# LineSense.net
KiCad netlist of a schematic drawn in EAGLE
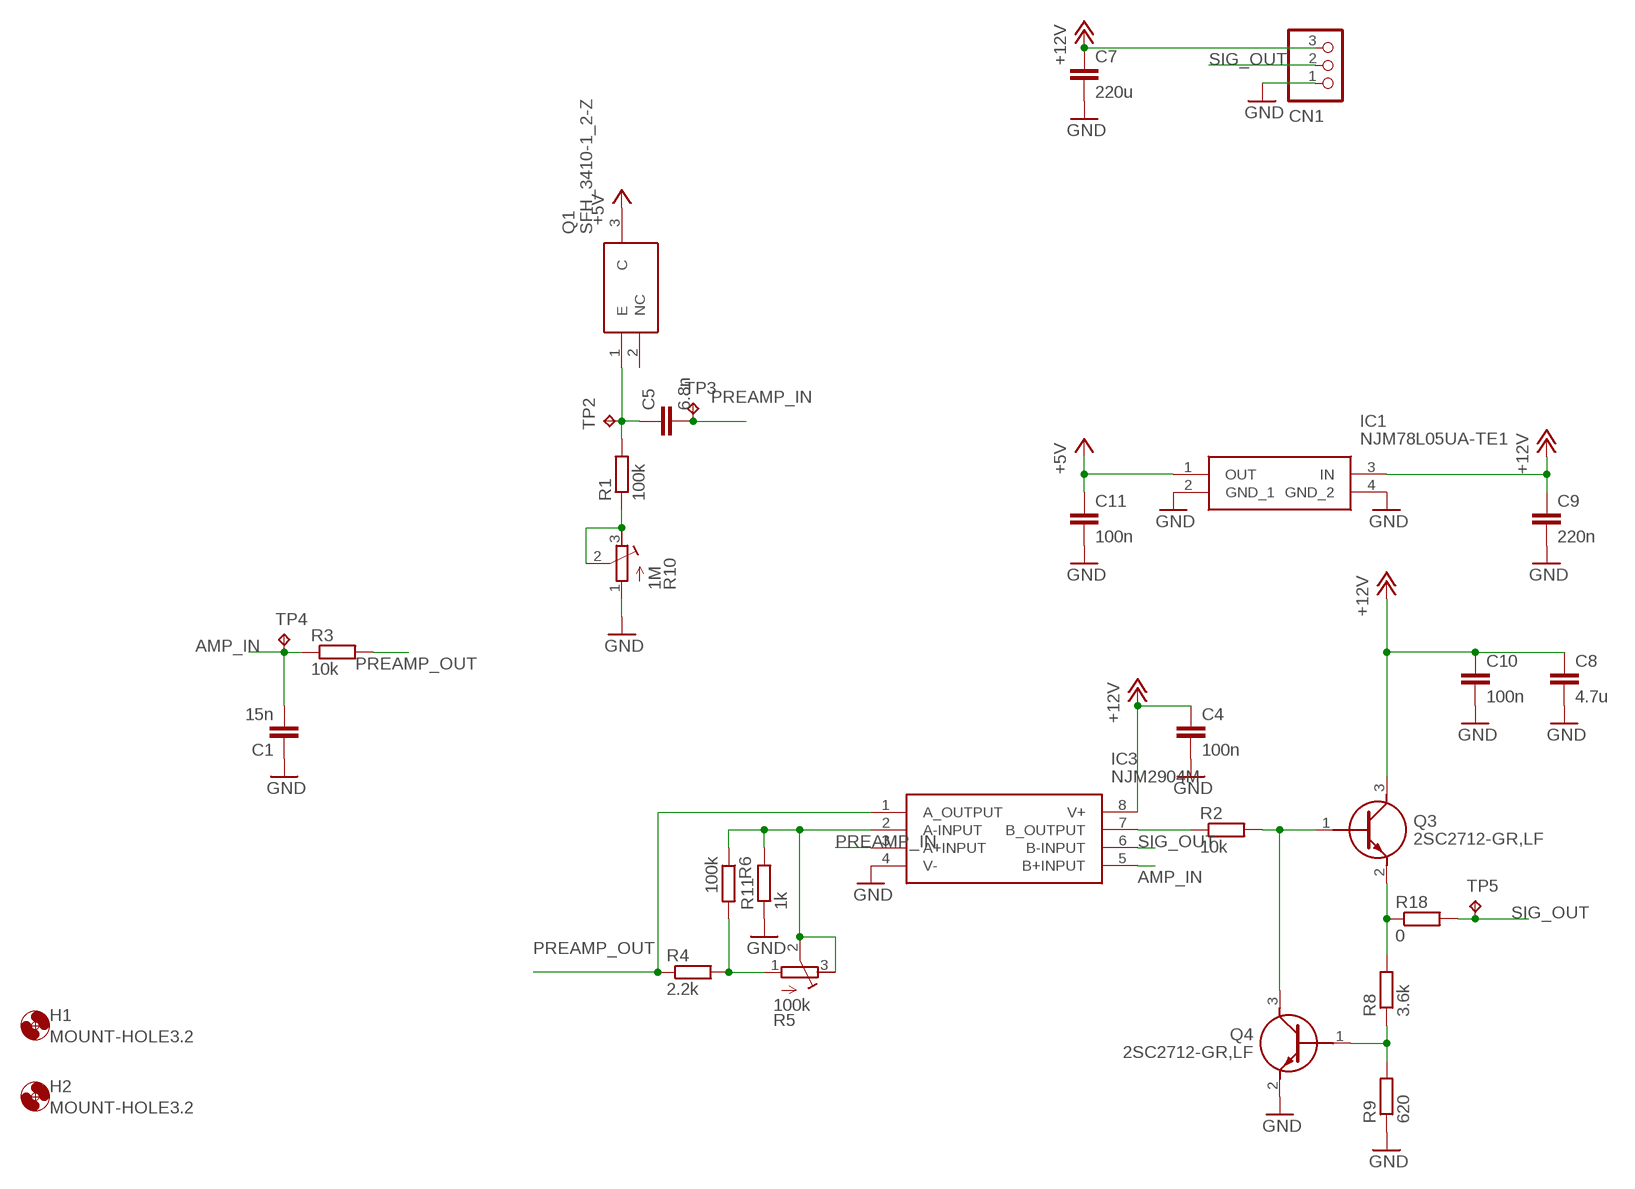
[diagram p0: schematic, sheet 1]
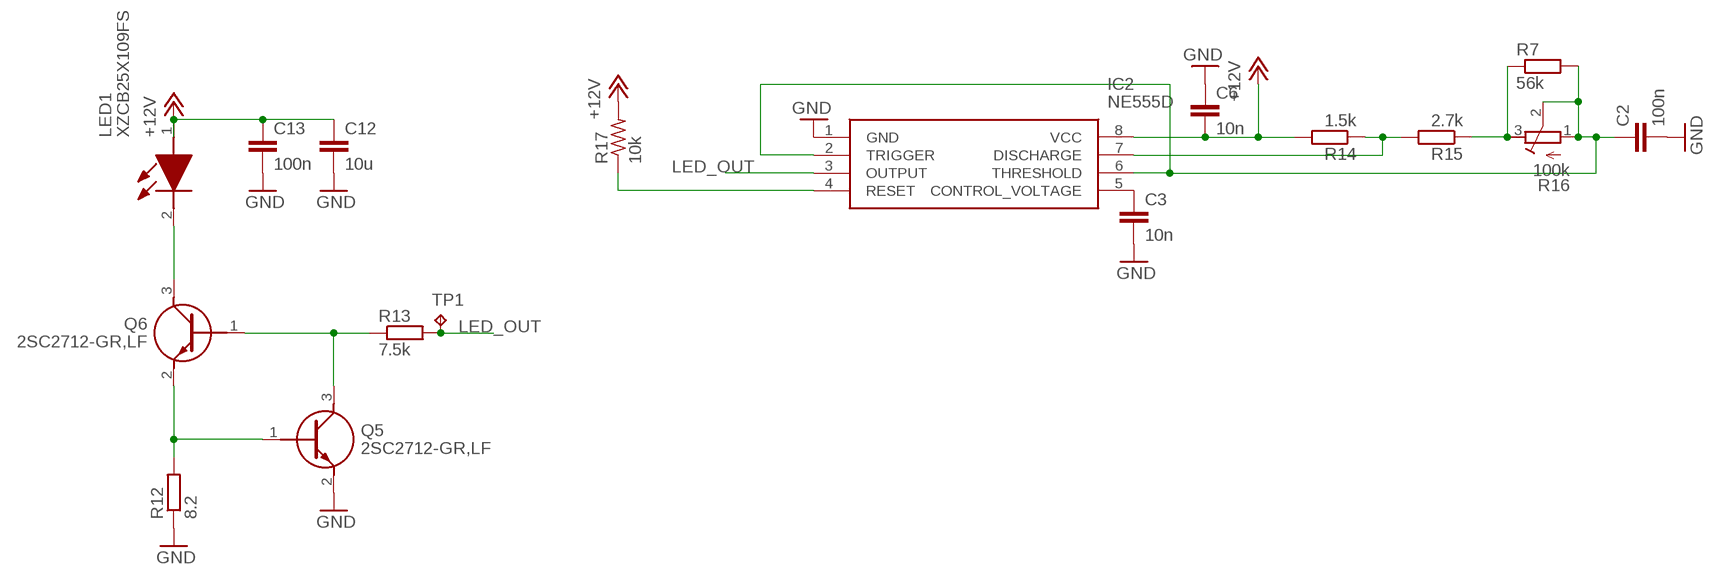
[diagram p1: schematic, sheet 2]

(export (version "E")
  (design (tool "Eeschema 10.0.6"))
  (components
    (comp (ref "C2")
      (value "100n")
      (footprint "eagle-import:C0603")
      (libsource (lib "eagle-import") (part "C-EUC0603"))
    )
    (comp (ref "C3")
      (value "10n")
      (footprint "eagle-import:C0603")
      (libsource (lib "eagle-import") (part "C-EUC0603"))
    )
    (comp (ref "C6")
      (value "10n")
      (footprint "eagle-import:C0603")
      (libsource (lib "eagle-import") (part "C-EUC0603"))
    )
    (comp (ref "C12")
      (value "10u")
      (footprint "eagle-import:C1210")
      (libsource (lib "eagle-import") (part "C-EUC1210"))
    )
    (comp (ref "C13")
      (value "100n")
      (footprint "eagle-import:C0603")
      (libsource (lib "eagle-import") (part "C-EUC0603"))
    )
    (comp (ref "IC2")
      (value "NE555D")
      (footprint "eagle-import:SOIC127P600X200-8N")
      (fields (field (name "MOUSER_PART_NUMBER") "512-NE555D"))
      (libsource (lib "eagle-import") (part "NE555D"))
    )
    (comp (ref "LED1")
      (value "XZCB25X109FS")
      (footprint "eagle-import:XZCB25X109FS")
      (libsource (lib "eagle-import") (part "XZCB25X109FS"))
    )
    (comp (ref "Q5")
      (value "2SC2712-GR,LF")
      (footprint "eagle-import:SSM3J334RLF")
      (fields (field (name "MOUSER_PART_NUMBER") "757-2SC2712-GRLF"))
      (libsource (lib "eagle-import") (part "2SC2712-GR,LF"))
    )
    (comp (ref "Q6")
      (value "2SC2712-GR,LF")
      (footprint "eagle-import:SSM3J334RLF")
      (fields (field (name "MOUSER_PART_NUMBER") "757-2SC2712-GRLF"))
      (libsource (lib "eagle-import") (part "2SC2712-GR,LF"))
    )
    (comp (ref "R7")
      (value "56k")
      (footprint "eagle-import:R0603")
      (libsource (lib "eagle-import") (part "R-EU_R0603"))
    )
    (comp (ref "R12")
      (value "8.2")
      (footprint "eagle-import:R0603")
      (libsource (lib "eagle-import") (part "R-EU_R0603"))
    )
    (comp (ref "R13")
      (value "7.5k")
      (footprint "eagle-import:R0603")
      (libsource (lib "eagle-import") (part "R-EU_R0603"))
    )
    (comp (ref "R14")
      (value "1.5k")
      (footprint "eagle-import:R0603")
      (libsource (lib "eagle-import") (part "R-EU_R0603"))
    )
    (comp (ref "R15")
      (value "2.7k")
      (footprint "eagle-import:R0603")
      (libsource (lib "eagle-import") (part "R-EU_R0603"))
    )
    (comp (ref "R16")
      (value "100k")
      (footprint "eagle-import:RTRIM3339P")
      (libsource (lib "eagle-import") (part "R-TRIMM3339P"))
    )
    (comp (ref "R17")
      (value "10k")
      (footprint "eagle-import:R0603")
      (libsource (lib "eagle-import") (part "R-US_R0603"))
    )
    (comp (ref "TP1")
      (value "TPB1,27")
      (footprint "eagle-import:B1,27")
      (libsource (lib "eagle-import") (part "TPB1,27"))
    )
    (comp (ref "C1")
      (value "15n")
      (footprint "eagle-import:C0603")
      (libsource (lib "eagle-import") (part "C-EUC0603"))
    )
    (comp (ref "C4")
      (value "100n")
      (footprint "eagle-import:C0603")
      (libsource (lib "eagle-import") (part "C-EUC0603"))
    )
    (comp (ref "C5")
      (value "6.8n")
      (footprint "eagle-import:C0603")
      (libsource (lib "eagle-import") (part "C-EUC0603"))
    )
    (comp (ref "C7")
      (value "220u")
      (footprint "eagle-import:C025-025X050")
      (libsource (lib "eagle-import") (part "C-EU025-025X050"))
    )
    (comp (ref "C8")
      (value "4.7u")
      (footprint "eagle-import:C1210")
      (libsource (lib "eagle-import") (part "C-EUC1210"))
    )
    (comp (ref "C9")
      (value "220n")
      (footprint "eagle-import:C0603")
      (libsource (lib "eagle-import") (part "C-EUC0603"))
    )
    (comp (ref "C10")
      (value "100n")
      (footprint "eagle-import:C0603")
      (libsource (lib "eagle-import") (part "C-EUC0603"))
    )
    (comp (ref "C11")
      (value "100n")
      (footprint "eagle-import:C0603")
      (libsource (lib "eagle-import") (part "C-EUC0603"))
    )
    (comp (ref "CN1")
      (value "S3B-XH-A")
      (footprint "eagle-import:S3B-XH-A")
      (libsource (lib "eagle-import") (part "S3B-XH-A"))
    )
    (comp (ref "H1")
      (value "MOUNT-HOLE3.2")
      (footprint "eagle-import:3,2")
      (libsource (lib "eagle-import") (part "MOUNT-HOLE3.2"))
    )
    (comp (ref "H2")
      (value "MOUNT-HOLE3.2")
      (footprint "eagle-import:3,2")
      (libsource (lib "eagle-import") (part "MOUNT-HOLE3.2"))
    )
    (comp (ref "IC1")
      (value "NJM78L05UA-TE1")
      (footprint "eagle-import:SOT-89-3")
      (fields (field (name "MOUSER_PART_NUMBER") "513-NJM78L05UA-TE1"))
      (libsource (lib "eagle-import") (part "NJM78L05UA-TE1"))
    )
    (comp (ref "IC3")
      (value "NJM2904M")
      (footprint "eagle-import:SOIC127P680X200-8N")
      (fields (field (name "MOUSER_PART_NUMBER") "513-NJM2904M"))
      (libsource (lib "eagle-import") (part "NJM2904M"))
    )
    (comp (ref "Q1")
      (value "SFH_3410-1_2-Z")
      (footprint "eagle-import:SFH341012Z")
      (fields
        (field (name "ARROW_PART_NUMBER") "SFH 3410-1/2-Z")
        (field (name "MOUSER_PART_NUMBER") "720-SFH3410-1/2-Z")
      )
      (libsource (lib "eagle-import") (part "SFH_3410-1_2-Z"))
    )
    (comp (ref "Q3")
      (value "2SC2712-GR,LF")
      (footprint "eagle-import:SSM3J334RLF")
      (fields (field (name "MOUSER_PART_NUMBER") "757-2SC2712-GRLF"))
      (libsource (lib "eagle-import") (part "2SC2712-GR,LF"))
    )
    (comp (ref "Q4")
      (value "2SC2712-GR,LF")
      (footprint "eagle-import:SSM3J334RLF")
      (fields (field (name "MOUSER_PART_NUMBER") "757-2SC2712-GRLF"))
      (libsource (lib "eagle-import") (part "2SC2712-GR,LF"))
    )
    (comp (ref "R1")
      (value "100k")
      (footprint "eagle-import:R0603")
      (libsource (lib "eagle-import") (part "R-EU_R0603"))
    )
    (comp (ref "R2")
      (value "10k")
      (footprint "eagle-import:R0603")
      (libsource (lib "eagle-import") (part "R-EU_R0603"))
    )
    (comp (ref "R3")
      (value "10k")
      (footprint "eagle-import:R0603")
      (libsource (lib "eagle-import") (part "R-EU_R0603"))
    )
    (comp (ref "R4")
      (value "2.2k")
      (footprint "eagle-import:R0603")
      (libsource (lib "eagle-import") (part "R-EU_R0603"))
    )
    (comp (ref "R5")
      (value "100k")
      (footprint "eagle-import:RTRIM3339P")
      (libsource (lib "eagle-import") (part "R-TRIMM3339P"))
    )
    (comp (ref "R6")
      (value "100k")
      (footprint "eagle-import:R0603")
      (libsource (lib "eagle-import") (part "R-EU_R0603"))
    )
    (comp (ref "R8")
      (value "3.6k")
      (footprint "eagle-import:R0603")
      (libsource (lib "eagle-import") (part "R-EU_R0603"))
    )
    (comp (ref "R9")
      (value "620")
      (footprint "eagle-import:R0603")
      (libsource (lib "eagle-import") (part "R-EU_R0603"))
    )
    (comp (ref "R10")
      (value "1M")
      (footprint "eagle-import:RTRIM3339P")
      (libsource (lib "eagle-import") (part "R-TRIMM3339P"))
    )
    (comp (ref "R11")
      (value "1k")
      (footprint "eagle-import:R0603")
      (libsource (lib "eagle-import") (part "R-EU_R0603"))
    )
    (comp (ref "R18")
      (value "0")
      (footprint "eagle-import:R0603")
      (libsource (lib "eagle-import") (part "R-EU_R0603"))
    )
    (comp (ref "TP2")
      (value "TPB1,27")
      (footprint "eagle-import:B1,27")
      (libsource (lib "eagle-import") (part "TPB1,27"))
    )
    (comp (ref "TP3")
      (value "TPB1,27")
      (footprint "eagle-import:B1,27")
      (libsource (lib "eagle-import") (part "TPB1,27"))
    )
    (comp (ref "TP4")
      (value "TPB1,27")
      (footprint "eagle-import:B1,27")
      (libsource (lib "eagle-import") (part "TPB1,27"))
    )
    (comp (ref "TP5")
      (value "TPB1,27")
      (footprint "eagle-import:B1,27")
      (libsource (lib "eagle-import") (part "TPB1,27"))
    )
  )
  (nets
    (net (code "1") (name "+5V") (class "Default")
      (node (ref "C11") (pin "1") (pinfunction "1_1") (pintype "passive"))
      (node (ref "IC1") (pin "1") (pinfunction "OUT_1") (pintype "bidirectional"))
      (node (ref "Q1") (pin "3") (pinfunction "C_3") (pintype "bidirectional"))
    )
    (net (code "2") (name "+12V") (class "Default")
      (node (ref "C10") (pin "1") (pinfunction "1_1") (pintype "passive"))
      (node (ref "C12") (pin "1") (pinfunction "1_1") (pintype "passive"))
      (node (ref "C13") (pin "1") (pinfunction "1_1") (pintype "passive"))
      (node (ref "C4") (pin "1") (pinfunction "1_1") (pintype "passive"))
      (node (ref "C6") (pin "2") (pinfunction "2_2") (pintype "passive"))
      (node (ref "C7") (pin "1") (pinfunction "1_1") (pintype "passive"))
      (node (ref "C8") (pin "1") (pinfunction "1_1") (pintype "passive"))
      (node (ref "C9") (pin "1") (pinfunction "1_1") (pintype "passive"))
      (node (ref "CN1") (pin "3") (pinfunction "3_3") (pintype "passive"))
      (node (ref "IC1") (pin "3") (pinfunction "IN_3") (pintype "bidirectional"))
      (node (ref "IC2") (pin "8") (pinfunction "VCC_8") (pintype "bidirectional"))
      (node (ref "IC3") (pin "8") (pinfunction "V+_8") (pintype "bidirectional"))
      (node (ref "LED1") (pin "1") (pinfunction "A_1") (pintype "bidirectional"))
      (node (ref "Q3") (pin "3") (pinfunction "C_3") (pintype "bidirectional"))
      (node (ref "R14") (pin "2") (pinfunction "2_2") (pintype "passive"))
      (node (ref "R17") (pin "2") (pinfunction "2_2") (pintype "passive"))
    )
    (net (code "3") (name "AMP_IN") (class "Default")
      (node (ref "C1") (pin "2") (pinfunction "2_2") (pintype "passive"))
      (node (ref "IC3") (pin "5") (pinfunction "B+INPUT_5") (pintype "bidirectional"))
      (node (ref "R3") (pin "1") (pinfunction "1_1") (pintype "passive"))
      (node (ref "TP4") (pin "TP") (pinfunction "TP_TP") (pintype "input"))
    )
    (net (code "4") (name "GND") (class "Default")
      (node (ref "C1") (pin "1") (pinfunction "1_1") (pintype "passive"))
      (node (ref "C10") (pin "2") (pinfunction "2_2") (pintype "passive"))
      (node (ref "C11") (pin "2") (pinfunction "2_2") (pintype "passive"))
      (node (ref "C12") (pin "2") (pinfunction "2_2") (pintype "passive"))
      (node (ref "C13") (pin "2") (pinfunction "2_2") (pintype "passive"))
      (node (ref "C2") (pin "2") (pinfunction "2_2") (pintype "passive"))
      (node (ref "C3") (pin "2") (pinfunction "2_2") (pintype "passive"))
      (node (ref "C4") (pin "2") (pinfunction "2_2") (pintype "passive"))
      (node (ref "C6") (pin "1") (pinfunction "1_1") (pintype "passive"))
      (node (ref "C7") (pin "2") (pinfunction "2_2") (pintype "passive"))
      (node (ref "C8") (pin "2") (pinfunction "2_2") (pintype "passive"))
      (node (ref "C9") (pin "2") (pinfunction "2_2") (pintype "passive"))
      (node (ref "CN1") (pin "1") (pinfunction "1_1") (pintype "passive"))
      (node (ref "IC1") (pin "2") (pinfunction "GND_1_2") (pintype "bidirectional"))
      (node (ref "IC1") (pin "4") (pinfunction "GND_2_4") (pintype "bidirectional"))
      (node (ref "IC2") (pin "1") (pinfunction "GND_1") (pintype "bidirectional"))
      (node (ref "IC3") (pin "4") (pinfunction "V-_4") (pintype "bidirectional"))
      (node (ref "Q4") (pin "2") (pinfunction "E_2") (pintype "bidirectional"))
      (node (ref "Q5") (pin "2") (pinfunction "E_2") (pintype "bidirectional"))
      (node (ref "R10") (pin "1") (pinfunction "A_1") (pintype "passive"))
      (node (ref "R11") (pin "1") (pinfunction "1_1") (pintype "passive"))
      (node (ref "R12") (pin "1") (pinfunction "1_1") (pintype "passive"))
      (node (ref "R9") (pin "1") (pinfunction "1_1") (pintype "passive"))
    )
    (net (code "5") (name "LED_OUT") (class "Default")
      (node (ref "IC2") (pin "3") (pinfunction "OUTPUT_3") (pintype "bidirectional"))
      (node (ref "R13") (pin "2") (pinfunction "2_2") (pintype "passive"))
      (node (ref "TP1") (pin "TP") (pinfunction "TP_TP") (pintype "input"))
    )
    (net (code "6") (name "Net-(IC2-CONTROL_VOLTAGE)") (class "Default")
      (node (ref "C3") (pin "1") (pinfunction "1_1") (pintype "passive"))
      (node (ref "IC2") (pin "5") (pinfunction "CONTROL_VOLTAGE_5") (pintype "bidirectional"))
    )
    (net (code "7") (name "Net-(IC2-DISCHARGE)") (class "Default")
      (node (ref "IC2") (pin "7") (pinfunction "DISCHARGE_7") (pintype "bidirectional"))
      (node (ref "R14") (pin "1") (pinfunction "1_1") (pintype "passive"))
      (node (ref "R15") (pin "2") (pinfunction "2_2") (pintype "passive"))
    )
    (net (code "8") (name "Net-(IC2-RESET)") (class "Default")
      (node (ref "IC2") (pin "4") (pinfunction "RESET_4") (pintype "bidirectional"))
      (node (ref "R17") (pin "1") (pinfunction "1_1") (pintype "passive"))
    )
    (net (code "9") (name "Net-(IC2-THRESHOLD)") (class "Default")
      (node (ref "C2") (pin "1") (pinfunction "1_1") (pintype "passive"))
      (node (ref "IC2") (pin "2") (pinfunction "TRIGGER_2") (pintype "bidirectional"))
      (node (ref "IC2") (pin "6") (pinfunction "THRESHOLD_6") (pintype "bidirectional"))
      (node (ref "R16") (pin "1") (pinfunction "A_1") (pintype "passive"))
      (node (ref "R16") (pin "2") (pinfunction "S_2") (pintype "passive"))
      (node (ref "R7") (pin "2") (pinfunction "2_2") (pintype "passive"))
    )
    (net (code "10") (name "Net-(IC3-A-INPUT)") (class "Default")
      (node (ref "IC3") (pin "2") (pinfunction "A-INPUT_2") (pintype "bidirectional"))
      (node (ref "R11") (pin "2") (pinfunction "2_2") (pintype "passive"))
      (node (ref "R5") (pin "2") (pinfunction "S_2") (pintype "passive"))
      (node (ref "R5") (pin "3") (pinfunction "E_3") (pintype "passive"))
      (node (ref "R6") (pin "1") (pinfunction "1_1") (pintype "passive"))
    )
    (net (code "11") (name "Net-(IC3-B_OUTPUT)") (class "Default")
      (node (ref "IC3") (pin "7") (pinfunction "B_OUTPUT_7") (pintype "bidirectional"))
      (node (ref "R2") (pin "1") (pinfunction "1_1") (pintype "passive"))
    )
    (net (code "12") (name "Net-(LED1-K)") (class "Default")
      (node (ref "LED1") (pin "2") (pinfunction "K_2") (pintype "bidirectional"))
      (node (ref "Q6") (pin "3") (pinfunction "C_3") (pintype "bidirectional"))
    )
    (net (code "13") (name "Net-(Q1-E)") (class "Default")
      (node (ref "C5") (pin "1") (pinfunction "1_1") (pintype "passive"))
      (node (ref "Q1") (pin "1") (pinfunction "E_1") (pintype "bidirectional"))
      (node (ref "R1") (pin "2") (pinfunction "2_2") (pintype "passive"))
      (node (ref "TP2") (pin "TP") (pinfunction "TP_TP") (pintype "input"))
    )
    (net (code "14") (name "Net-(Q3-B)") (class "Default")
      (node (ref "Q3") (pin "1") (pinfunction "B_1") (pintype "bidirectional"))
      (node (ref "Q4") (pin "3") (pinfunction "C_3") (pintype "bidirectional"))
      (node (ref "R2") (pin "2") (pinfunction "2_2") (pintype "passive"))
    )
    (net (code "15") (name "Net-(Q3-E)") (class "Default")
      (node (ref "Q3") (pin "2") (pinfunction "E_2") (pintype "bidirectional"))
      (node (ref "R18") (pin "1") (pinfunction "1_1") (pintype "passive"))
      (node (ref "R8") (pin "2") (pinfunction "2_2") (pintype "passive"))
    )
    (net (code "16") (name "Net-(Q4-B)") (class "Default")
      (node (ref "Q4") (pin "1") (pinfunction "B_1") (pintype "bidirectional"))
      (node (ref "R8") (pin "1") (pinfunction "1_1") (pintype "passive"))
      (node (ref "R9") (pin "2") (pinfunction "2_2") (pintype "passive"))
    )
    (net (code "17") (name "Net-(Q5-B)") (class "Default")
      (node (ref "Q5") (pin "1") (pinfunction "B_1") (pintype "bidirectional"))
      (node (ref "Q6") (pin "2") (pinfunction "E_2") (pintype "bidirectional"))
      (node (ref "R12") (pin "2") (pinfunction "2_2") (pintype "passive"))
    )
    (net (code "18") (name "Net-(Q5-C)") (class "Default")
      (node (ref "Q5") (pin "3") (pinfunction "C_3") (pintype "bidirectional"))
      (node (ref "Q6") (pin "1") (pinfunction "B_1") (pintype "bidirectional"))
      (node (ref "R13") (pin "1") (pinfunction "1_1") (pintype "passive"))
    )
    (net (code "19") (name "Net-(R5-A)") (class "Default")
      (node (ref "R4") (pin "2") (pinfunction "2_2") (pintype "passive"))
      (node (ref "R5") (pin "1") (pinfunction "A_1") (pintype "passive"))
      (node (ref "R6") (pin "2") (pinfunction "2_2") (pintype "passive"))
    )
    (net (code "20") (name "Net-(R10-E)") (class "Default")
      (node (ref "R1") (pin "1") (pinfunction "1_1") (pintype "passive"))
      (node (ref "R10") (pin "2") (pinfunction "S_2") (pintype "passive"))
      (node (ref "R10") (pin "3") (pinfunction "E_3") (pintype "passive"))
    )
    (net (code "21") (name "Net-(R16-E)") (class "Default")
      (node (ref "R15") (pin "1") (pinfunction "1_1") (pintype "passive"))
      (node (ref "R16") (pin "3") (pinfunction "E_3") (pintype "passive"))
      (node (ref "R7") (pin "1") (pinfunction "1_1") (pintype "passive"))
    )
    (net (code "22") (name "PREAMP_IN") (class "Default")
      (node (ref "C5") (pin "2") (pinfunction "2_2") (pintype "passive"))
      (node (ref "IC3") (pin "3") (pinfunction "A+INPUT_3") (pintype "bidirectional"))
      (node (ref "TP3") (pin "TP") (pinfunction "TP_TP") (pintype "input"))
    )
    (net (code "23") (name "PREAMP_OUT") (class "Default")
      (node (ref "IC3") (pin "1") (pinfunction "A_OUTPUT_1") (pintype "bidirectional"))
      (node (ref "R3") (pin "2") (pinfunction "2_2") (pintype "passive"))
      (node (ref "R4") (pin "1") (pinfunction "1_1") (pintype "passive"))
    )
    (net (code "24") (name "SIG_OUT") (class "Default")
      (node (ref "CN1") (pin "2") (pinfunction "2_2") (pintype "passive"))
      (node (ref "IC3") (pin "6") (pinfunction "B-INPUT_6") (pintype "bidirectional"))
      (node (ref "R18") (pin "2") (pinfunction "2_2") (pintype "passive"))
      (node (ref "TP5") (pin "TP") (pinfunction "TP_TP") (pintype "input"))
    )
    (net (code "25") (name "unconnected-(Q1-NC-Pad2)") (class "Default")
      (node (ref "Q1") (pin "2") (pinfunction "NC_2") (pintype "no_connect"))
    )
  )
)
